# Tilt-NE555-C_AAA.net
KiCad netlist of a schematic drawn in EAGLE
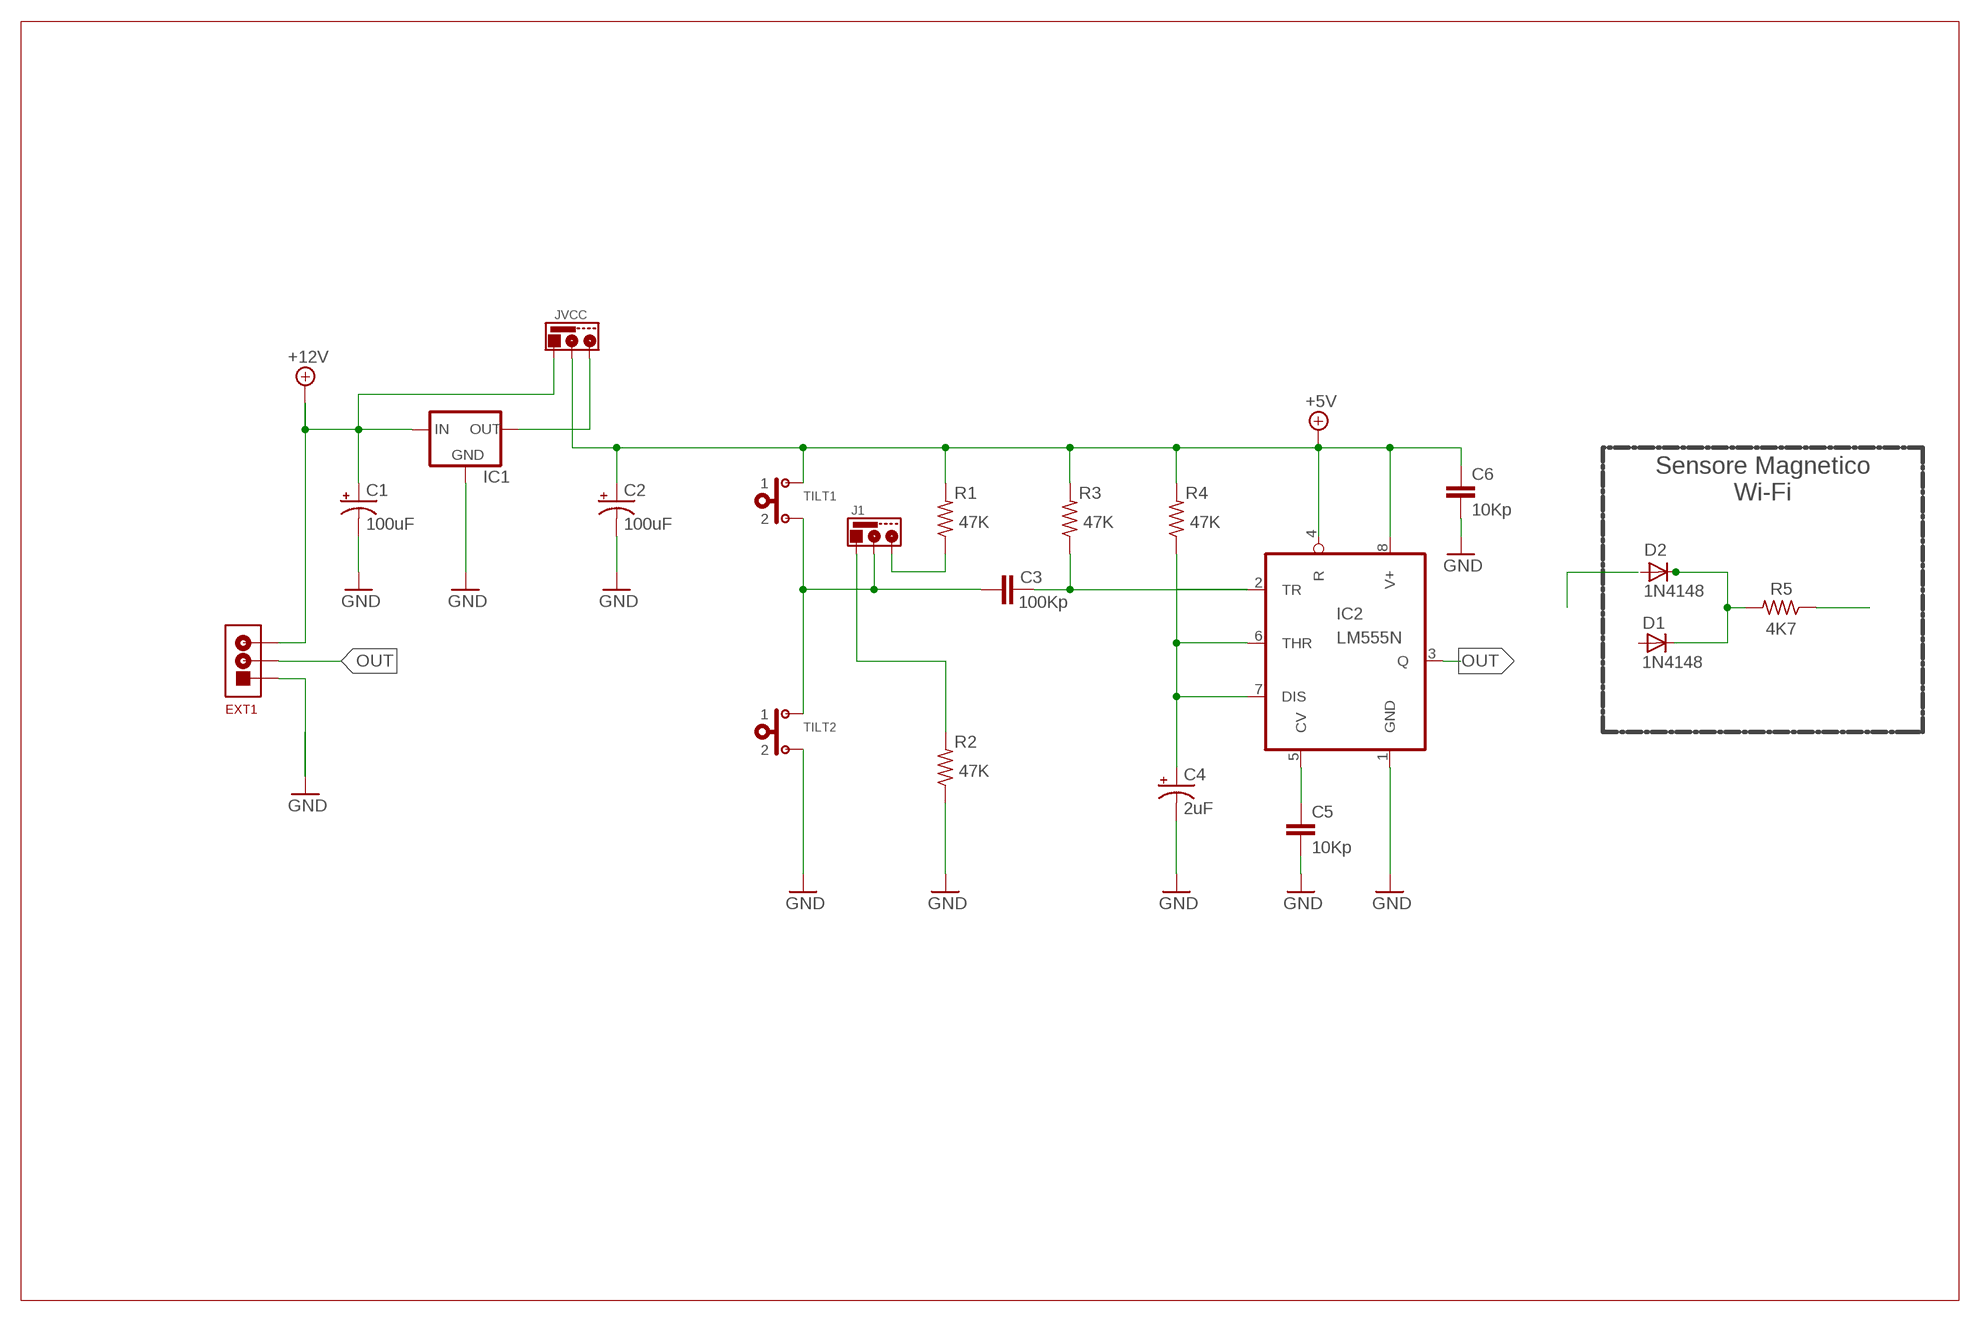
[diagram p0: schematic, sheet 1]

(export (version "E")
  (design (tool "Eeschema 10.0.6"))
  (components
    (comp (ref "C1")
      (value "100uF")
      (footprint "eagle-import:E5-5")
      (libsource (lib "eagle-import") (part "CPOL-USE5-5"))
    )
    (comp (ref "C2")
      (value "100uF")
      (footprint "eagle-import:E5-5")
      (libsource (lib "eagle-import") (part "CPOL-USE5-5"))
    )
    (comp (ref "C3")
      (value "100Kp")
      (footprint "eagle-import:C050-035X075")
      (libsource (lib "eagle-import") (part "C-EU050-035X075"))
    )
    (comp (ref "C4")
      (value "2uF")
      (footprint "eagle-import:E5-5")
      (libsource (lib "eagle-import") (part "CPOL-USE5-5"))
    )
    (comp (ref "C5")
      (value "10Kp")
      (footprint "eagle-import:C050-045X075")
      (libsource (lib "eagle-import") (part "C-EU050-045X075"))
    )
    (comp (ref "C6")
      (value "10Kp")
      (footprint "eagle-import:C050-045X075")
      (libsource (lib "eagle-import") (part "C-EU050-045X075"))
    )
    (comp (ref "D1")
      (value "1N4148")
      (footprint "eagle-import:DO35-10")
      (libsource (lib "eagle-import") (part "1N4148DO35-10"))
    )
    (comp (ref "D2")
      (value "1N4148")
      (footprint "eagle-import:DO35-10")
      (libsource (lib "eagle-import") (part "1N4148DO35-10"))
    )
    (comp (ref "EXT1")
      (value "MAMMUTH03")
      (footprint "eagle-import:MAMMUTH03")
      (libsource (lib "eagle-import") (part "MAMMUTH03"))
    )
    (comp (ref "IC1")
      (value "78LXX")
      (footprint "eagle-import:78LXX")
      (libsource (lib "eagle-import") (part "78LXX"))
    )
    (comp (ref "IC2")
      (value "LM555N")
      (footprint "eagle-import:DIL08")
      (libsource (lib "eagle-import") (part "555NLM"))
    )
    (comp (ref "J1")
      (value "JUMPER3")
      (footprint "eagle-import:SIP03")
      (libsource (lib "eagle-import") (part "JUMPER3"))
    )
    (comp (ref "JVCC")
      (value "JUMPER3")
      (footprint "eagle-import:SIP03")
      (libsource (lib "eagle-import") (part "JUMPER3"))
    )
    (comp (ref "R1")
      (value "47K")
      (footprint "eagle-import:0207_12")
      (libsource (lib "eagle-import") (part "R-US_0207/12"))
    )
    (comp (ref "R2")
      (value "47K")
      (footprint "eagle-import:0207_12")
      (libsource (lib "eagle-import") (part "R-US_0207/12"))
    )
    (comp (ref "R3")
      (value "47K")
      (footprint "eagle-import:0207_12")
      (libsource (lib "eagle-import") (part "R-US_0207/12"))
    )
    (comp (ref "R4")
      (value "47K")
      (footprint "eagle-import:0207_12")
      (libsource (lib "eagle-import") (part "R-US_0207/12"))
    )
    (comp (ref "R5")
      (value "4K7")
      (footprint "eagle-import:0207_12")
      (libsource (lib "eagle-import") (part "R-US_0207/12"))
    )
    (comp (ref "TILT1")
      (value "PULSANTENO")
      (footprint "eagle-import:SIP02")
      (libsource (lib "eagle-import") (part "PULSANTENO"))
    )
    (comp (ref "TILT2")
      (value "PULSANTENO")
      (footprint "eagle-import:SIP02")
      (libsource (lib "eagle-import") (part "PULSANTENO"))
    )
  )
  (nets
    (net (code "1") (name "+5V") (class "Default")
      (node (ref "C2") (pin "+") (pinfunction "+_+") (pintype "passive"))
      (node (ref "C6") (pin "1") (pinfunction "1_1") (pintype "passive"))
      (node (ref "IC2") (pin "4") (pinfunction "R_4") (pintype "input"))
      (node (ref "IC2") (pin "8") (pinfunction "V+_8") (pintype "power_in"))
      (node (ref "JVCC") (pin "1") (pinfunction "2_1") (pintype "bidirectional"))
      (node (ref "R1") (pin "2") (pinfunction "2_2") (pintype "passive"))
      (node (ref "R3") (pin "2") (pinfunction "2_2") (pintype "passive"))
      (node (ref "R4") (pin "2") (pinfunction "2_2") (pintype "passive"))
      (node (ref "TILT1") (pin "1") (pinfunction "1_1") (pintype "bidirectional"))
    )
    (net (code "2") (name "+12V") (class "Default")
      (node (ref "C1") (pin "+") (pinfunction "+_+") (pintype "passive"))
      (node (ref "EXT1") (pin "P$3") (pinfunction "3_P$3") (pintype "bidirectional"))
      (node (ref "IC1") (pin "IN") (pinfunction "IN_IN") (pintype "input"))
      (node (ref "JVCC") (pin "2") (pinfunction "1_2") (pintype "bidirectional"))
    )
    (net (code "3") (name "GND") (class "Default")
      (node (ref "C1") (pin "-") (pinfunction "-_-") (pintype "passive"))
      (node (ref "C2") (pin "-") (pinfunction "-_-") (pintype "passive"))
      (node (ref "C4") (pin "-") (pinfunction "-_-") (pintype "passive"))
      (node (ref "C5") (pin "2") (pinfunction "2_2") (pintype "passive"))
      (node (ref "C6") (pin "2") (pinfunction "2_2") (pintype "passive"))
      (node (ref "EXT1") (pin "P$1") (pinfunction "1_P$1") (pintype "bidirectional"))
      (node (ref "IC1") (pin "GND") (pinfunction "GND_GND") (pintype "input"))
      (node (ref "IC2") (pin "1") (pinfunction "GND_1") (pintype "power_in"))
      (node (ref "R2") (pin "1") (pinfunction "1_1") (pintype "passive"))
      (node (ref "TILT2") (pin "2") (pinfunction "2_2") (pintype "bidirectional"))
    )
    (net (code "4") (name "Net-(D1-PadC)") (class "Default")
      (node (ref "D1") (pin "C") (pinfunction "C_C") (pintype "passive"))
      (node (ref "D2") (pin "C") (pinfunction "C_C") (pintype "passive"))
      (node (ref "R5") (pin "2") (pinfunction "2_2") (pintype "passive"))
    )
    (net (code "5") (name "Net-(IC1-PadOUT)") (class "Default")
      (node (ref "IC1") (pin "OUT") (pinfunction "OUT_OUT") (pintype "passive"))
      (node (ref "JVCC") (pin "3") (pinfunction "3_3") (pintype "bidirectional"))
    )
    (net (code "6") (name "Net-(IC2-CV)") (class "Default")
      (node (ref "C5") (pin "1") (pinfunction "1_1") (pintype "passive"))
      (node (ref "IC2") (pin "5") (pinfunction "CV_5") (pintype "input"))
    )
    (net (code "7") (name "Net-(IC2-DIS)") (class "Default")
      (node (ref "C4") (pin "+") (pinfunction "+_+") (pintype "passive"))
      (node (ref "IC2") (pin "6") (pinfunction "THR_6") (pintype "input"))
      (node (ref "IC2") (pin "7") (pinfunction "DIS_7") (pintype "input"))
      (node (ref "R4") (pin "1") (pinfunction "1_1") (pintype "passive"))
    )
    (net (code "8") (name "Net-(IC2-TR)") (class "Default")
      (node (ref "C3") (pin "2") (pinfunction "2_2") (pintype "passive"))
      (node (ref "IC2") (pin "2") (pinfunction "TR_2") (pintype "input"))
      (node (ref "R3") (pin "1") (pinfunction "1_1") (pintype "passive"))
    )
    (net (code "9") (name "Net-(J1-1)") (class "Default")
      (node (ref "J1") (pin "2") (pinfunction "1_2") (pintype "bidirectional"))
      (node (ref "R2") (pin "2") (pinfunction "2_2") (pintype "passive"))
    )
    (net (code "10") (name "Net-(J1-2)") (class "Default")
      (node (ref "C3") (pin "1") (pinfunction "1_1") (pintype "passive"))
      (node (ref "J1") (pin "1") (pinfunction "2_1") (pintype "bidirectional"))
      (node (ref "TILT1") (pin "2") (pinfunction "2_2") (pintype "bidirectional"))
      (node (ref "TILT2") (pin "1") (pinfunction "1_1") (pintype "bidirectional"))
    )
    (net (code "11") (name "Net-(J1-Pad3)") (class "Default")
      (node (ref "J1") (pin "3") (pinfunction "3_3") (pintype "bidirectional"))
      (node (ref "R1") (pin "1") (pinfunction "1_1") (pintype "passive"))
    )
    (net (code "12") (name "OUT") (class "Default")
      (node (ref "EXT1") (pin "P$2") (pinfunction "2_P$2") (pintype "bidirectional"))
      (node (ref "IC2") (pin "3") (pinfunction "Q_3") (pintype "output"))
    )
    (net (code "13") (name "unconnected-(D1-PadA)") (class "Default")
      (node (ref "D1") (pin "A") (pinfunction "A_A") (pintype "passive"))
    )
    (net (code "14") (name "unconnected-(D2-PadA)") (class "Default")
      (node (ref "D2") (pin "A") (pinfunction "A_A") (pintype "passive"))
    )
    (net (code "15") (name "unconnected-(R5-Pad1)") (class "Default")
      (node (ref "R5") (pin "1") (pinfunction "1_1") (pintype "passive"))
    )
  )
)
